# 3_pure60-WKL_mcu.net
KiCad netlist of a schematic drawn in Altium Designer
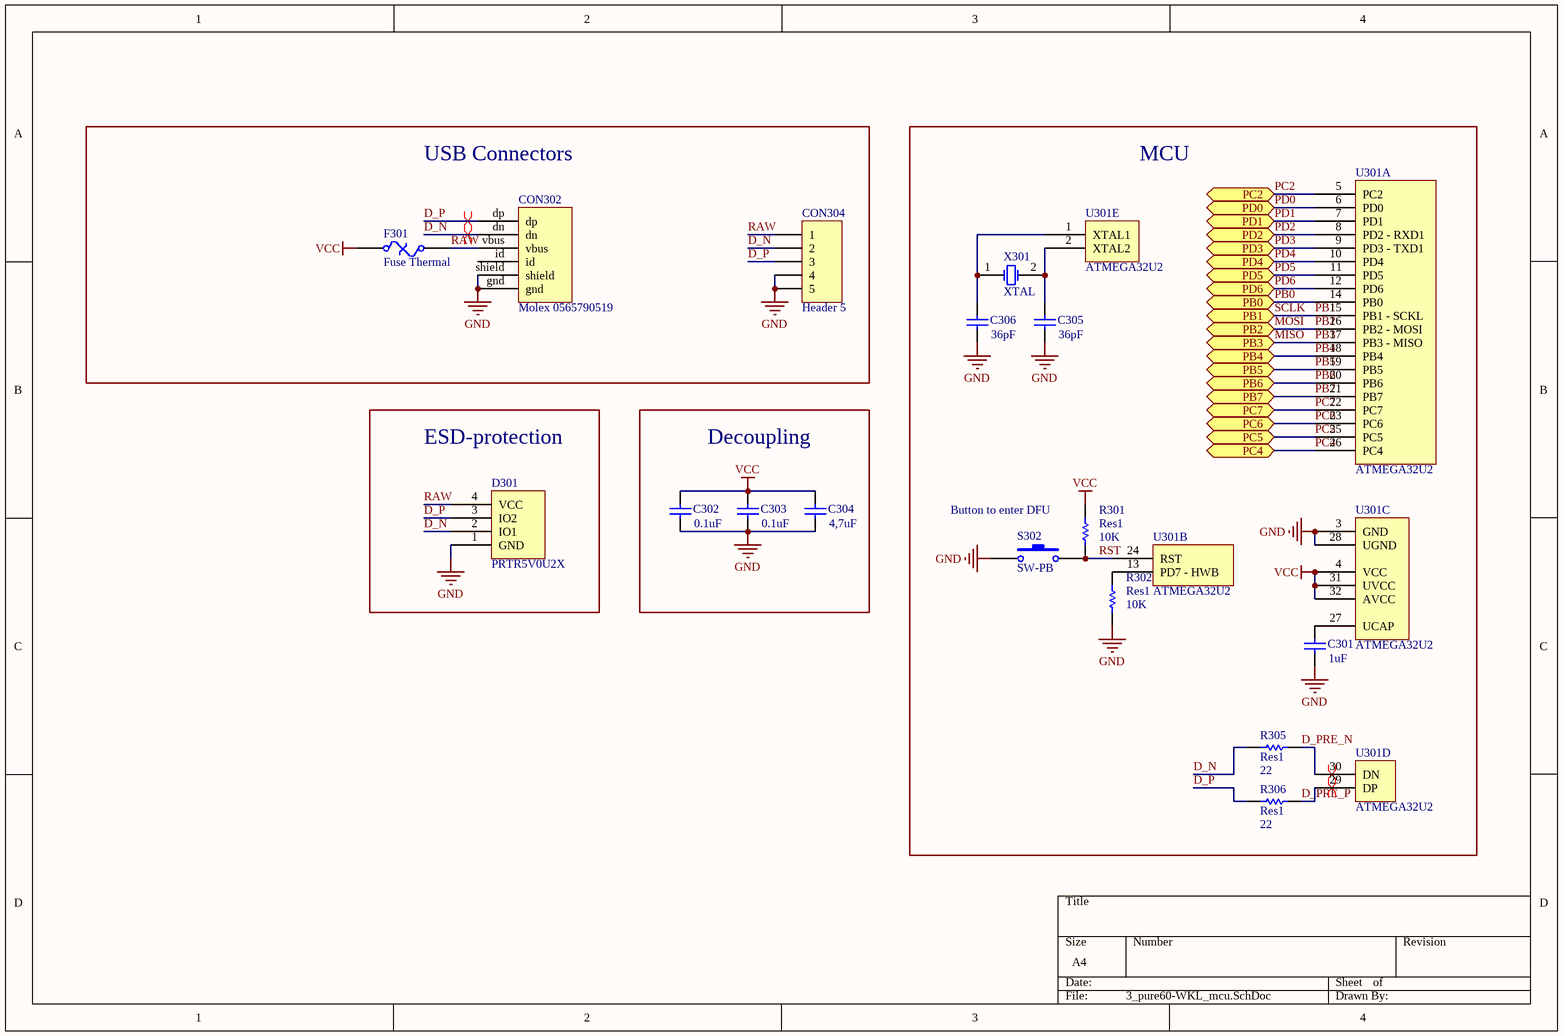
[diagram p0: 3_pure60-WKL_mcu.SchDoc]

(export (version "E")
  (design (tool "Eeschema 10.0.6"))
  (components
    (comp (ref "C301")
      (value "1uF")
      (footprint "C0603[1608]")
      (description "Capacitor")
      (fields (field (name "MFG") "KEMET") (field (name "MRF.PART") "CL10A105KB8NNNC"))
      (libsource (lib "Miscellaneous Devices") (part "Cap"))
    )
    (comp (ref "C302")
      (value "0.1uF")
      (footprint "C0603[1608]")
      (description "Capacitor")
      (fields (field (name "MFG") "KEMET") (field (name "MRF.PART") "CC0603KRX7R9BB104"))
      (libsource (lib "Miscellaneous Devices") (part "Cap"))
    )
    (comp (ref "C303")
      (value "0.1uF")
      (footprint "C0603[1608]")
      (description "Capacitor")
      (fields (field (name "MFG") "KEMET") (field (name "MRF.PART") "CC0603KRX7R9BB104"))
      (libsource (lib "Miscellaneous Devices") (part "Cap"))
    )
    (comp (ref "C304")
      (value "4,7uF")
      (footprint "C1206[3216]")
      (description "Capacitor")
      (fields (field (name "MFG") "KEMET") (field (name "MRF.PART") "1206B475K500NT"))
      (libsource (lib "Miscellaneous Devices") (part "Cap"))
    )
    (comp (ref "C305")
      (value "36pF")
      (footprint "C0603[1608]")
      (description "Capacitor")
      (fields (field (name "MFG") "KEMET") (field (name "MRF.PART") "CL10C360JB8NNNC"))
      (libsource (lib "Miscellaneous Devices") (part "Cap"))
    )
    (comp (ref "C306")
      (value "36pF")
      (footprint "C0603[1608]")
      (description "Capacitor")
      (fields (field (name "MFG") "KEMET") (field (name "MRF.PART") "CL10C360JB8NNNC"))
      (libsource (lib "Miscellaneous Devices") (part "Cap"))
    )
    (comp (ref "CON302")
      (value "Molex 0565790519")
      (footprint "Molex 0565790519")
      (libsource (lib "Keebs") (part "Molex 0565790519"))
    )
    (comp (ref "CON304")
      (value "Header 5")
      (footprint "JST SM04B-SRSS-TB")
      (description "JST for USB daughter board")
      (fields (field (name "MFG") "JST Sales America Inc.") (field (name "MRF.PART") "SM04B-SRSS-TB(LF)(SN)"))
      (libsource (lib "Miscellaneous Connectors") (part "Header 5"))
    )
    (comp (ref "D301")
      (value "PRTR5V0U2X")
      (footprint "SOT190P237X120-4N")
      (fields (field (name "MFG") "Nexperia USA Inc.") (field (name "MRF.PART") "UET14A05L03"))
      (libsource (lib "Schlib1") (part "PRTR5V0U2X"))
    )
    (comp (ref "F301")
      (value "Fuse Thermal")
      (footprint "C1206[3216]")
      (description "Thermal Fuse")
      (fields (field (name "MFG") "Bel Fuse Inc.") (field (name "MRF.PART") "ASMD1206-050"))
      (libsource (lib "Miscellaneous Devices") (part "Fuse Thermal"))
    )
    (comp (ref "R301")
      (value "Res1")
      (footprint "R0603[1608]")
      (description "Resistor")
      (fields
        (field (name "ALTIUM_VALUE") "10K")
        (field (name "MFG") "Panasonic Electronic Components")
        (field (name "MRF.PART") "0603WAF1002T5E")
      )
      (libsource (lib "Miscellaneous Devices") (part "Res1"))
    )
    (comp (ref "R302")
      (value "Res1")
      (footprint "R0603[1608]")
      (description "Resistor")
      (fields
        (field (name "ALTIUM_VALUE") "10K")
        (field (name "MFG") "Panasonic Electronic Components")
        (field (name "MRF.PART") "0603WAF1002T5E")
      )
      (libsource (lib "Miscellaneous Devices") (part "Res1"))
    )
    (comp (ref "R305")
      (value "Res1")
      (footprint "R0603[1608]")
      (description "Resistor")
      (fields
        (field (name "ALTIUM_VALUE") "22")
        (field (name "MFG") "Panasonic Electronic Components")
        (field (name "MRF.PART") "0603WAF220JT5E")
      )
      (libsource (lib "Miscellaneous Devices") (part "Res1"))
    )
    (comp (ref "R306")
      (value "Res1")
      (footprint "R0603[1608]")
      (description "Resistor")
      (fields
        (field (name "ALTIUM_VALUE") "22")
        (field (name "MFG") "Panasonic Electronic Components")
        (field (name "MRF.PART") "0603WAF220JT5E")
      )
      (libsource (lib "Miscellaneous Devices") (part "Res1"))
    )
    (comp (ref "S302")
      (value "SW-PB")
      (footprint "Combo switch")
      (description "Switch")
      (fields (field (name "MFG") "C&K") (field (name "MRF.PART") "TS-1187A-C-D-B"))
      (libsource (lib "Miscellaneous Devices") (part "SW-PB"))
    )
    (comp (ref "U301")
      (value "ATMEGA32U2")
      (footprint "ATMEGA32U2-QFN")
      (fields (field (name "MFG") "Microchip Technology") (field (name "MRF.PART") "ATMEGA32U2-MU"))
      (libsource (lib "") (part "ATMEGA32U2_1"))
    )
    (comp (ref "X301")
      (value "XTAL")
      (footprint "CTS 445-series crystal")
      (description "Crystal Oscillator")
      (fields (field (name "MRF.PART") "X503216MSB2GI"))
      (libsource (lib "Miscellaneous Devices") (part "XTAL"))
    )
  )
  (nets
    (net (code "1") (name "/D_N") (class "Default")
      (node (ref "CON302") (pin "dn") (pinfunction "dn_dn") (pintype "passive"))
      (node (ref "CON304") (pin "2") (pinfunction "2_2") (pintype "passive"))
      (node (ref "D301") (pin "2") (pinfunction "IO1_2") (pintype "passive"))
      (node (ref "R305") (pin "2") (pinfunction "2_2") (pintype "passive"))
    )
    (net (code "2") (name "/D_P") (class "Default")
      (node (ref "CON302") (pin "dp") (pinfunction "dp_dp") (pintype "passive"))
      (node (ref "CON304") (pin "3") (pinfunction "3_3") (pintype "passive"))
      (node (ref "D301") (pin "3") (pinfunction "IO2_3") (pintype "passive"))
      (node (ref "R306") (pin "2") (pinfunction "2_2") (pintype "passive"))
    )
    (net (code "3") (name "/D_PRE_N") (class "Default")
      (node (ref "R305") (pin "1") (pinfunction "1_1") (pintype "passive"))
      (node (ref "U301") (pin "30") (pinfunction "DN_30") (pintype "passive"))
    )
    (net (code "4") (name "/D_PRE_P") (class "Default")
      (node (ref "R306") (pin "1") (pinfunction "1_1") (pintype "passive"))
      (node (ref "U301") (pin "29") (pinfunction "DP_29") (pintype "passive"))
    )
    (net (code "5") (name "/MISO") (class "Default")
      (node (ref "U301") (pin "17") (pinfunction "PB3_-_MISO_17") (pintype "passive"))
    )
    (net (code "6") (name "/MOSI") (class "Default")
      (node (ref "U301") (pin "16") (pinfunction "PB2_-_MOSI_16") (pintype "passive"))
    )
    (net (code "7") (name "/PB0") (class "Default")
      (node (ref "U301") (pin "14") (pinfunction "PB0_14") (pintype "passive"))
    )
    (net (code "8") (name "/PB1") (class "Default")
      (node (ref "U301") (pin "15") (pinfunction "PB1_-_SCKL_15") (pintype "passive"))
    )
    (net (code "9") (name "/PB4") (class "Default")
      (node (ref "U301") (pin "18") (pinfunction "PB4_18") (pintype "passive"))
    )
    (net (code "10") (name "/PB5") (class "Default")
      (node (ref "U301") (pin "19") (pinfunction "PB5_19") (pintype "passive"))
    )
    (net (code "11") (name "/PB6") (class "Default")
      (node (ref "U301") (pin "20") (pinfunction "PB6_20") (pintype "passive"))
    )
    (net (code "12") (name "/PB7") (class "Default")
      (node (ref "U301") (pin "21") (pinfunction "PB7_21") (pintype "passive"))
    )
    (net (code "13") (name "/PC2") (class "Default")
      (node (ref "U301") (pin "5") (pinfunction "PC2_5") (pintype "passive"))
    )
    (net (code "14") (name "/PC4") (class "Default")
      (node (ref "U301") (pin "26") (pinfunction "PC4_26") (pintype "passive"))
    )
    (net (code "15") (name "/PC5") (class "Default")
      (node (ref "U301") (pin "25") (pinfunction "PC5_25") (pintype "passive"))
    )
    (net (code "16") (name "/PC6") (class "Default")
      (node (ref "U301") (pin "23") (pinfunction "PC6_23") (pintype "passive"))
    )
    (net (code "17") (name "/PC7") (class "Default")
      (node (ref "U301") (pin "22") (pinfunction "PC7_22") (pintype "passive"))
    )
    (net (code "18") (name "/PD0") (class "Default")
      (node (ref "U301") (pin "6") (pinfunction "PD0_6") (pintype "passive"))
    )
    (net (code "19") (name "/PD1") (class "Default")
      (node (ref "U301") (pin "7") (pinfunction "PD1_7") (pintype "passive"))
    )
    (net (code "20") (name "/PD2") (class "Default")
      (node (ref "U301") (pin "8") (pinfunction "PD2_-_RXD1_8") (pintype "passive"))
    )
    (net (code "21") (name "/PD3") (class "Default")
      (node (ref "U301") (pin "9") (pinfunction "PD3_-_TXD1_9") (pintype "passive"))
    )
    (net (code "22") (name "/PD4") (class "Default")
      (node (ref "U301") (pin "10") (pinfunction "PD4_10") (pintype "passive"))
    )
    (net (code "23") (name "/PD5") (class "Default")
      (node (ref "U301") (pin "11") (pinfunction "PD5_11") (pintype "passive"))
    )
    (net (code "24") (name "/PD6") (class "Default")
      (node (ref "U301") (pin "12") (pinfunction "PD6_12") (pintype "passive"))
    )
    (net (code "25") (name "/RAW") (class "Default")
      (node (ref "CON302") (pin "vbus") (pinfunction "vbus_vbus") (pintype "passive"))
      (node (ref "CON304") (pin "1") (pinfunction "1_1") (pintype "passive"))
      (node (ref "D301") (pin "4") (pinfunction "VCC_4") (pintype "passive"))
      (node (ref "F301") (pin "2") (pinfunction "2_2") (pintype "passive"))
    )
    (net (code "26") (name "/RST") (class "Default")
      (node (ref "R301") (pin "2") (pinfunction "2_2") (pintype "passive"))
      (node (ref "S302") (pin "2") (pinfunction "2_2") (pintype "passive"))
      (node (ref "U301") (pin "24") (pinfunction "RST_24") (pintype "passive"))
    )
    (net (code "27") (name "GND") (class "Default")
      (node (ref "C301") (pin "1") (pinfunction "1_1") (pintype "passive"))
      (node (ref "C302") (pin "1") (pinfunction "1_1") (pintype "passive"))
      (node (ref "C303") (pin "1") (pinfunction "1_1") (pintype "passive"))
      (node (ref "C304") (pin "1") (pinfunction "1_1") (pintype "passive"))
      (node (ref "C305") (pin "1") (pinfunction "1_1") (pintype "passive"))
      (node (ref "C306") (pin "1") (pinfunction "1_1") (pintype "passive"))
      (node (ref "CON302") (pin "gnd") (pinfunction "gnd_gnd") (pintype "passive"))
      (node (ref "CON302") (pin "shield") (pinfunction "shield_shield") (pintype "passive"))
      (node (ref "CON304") (pin "4") (pinfunction "4_4") (pintype "passive"))
      (node (ref "CON304") (pin "5") (pinfunction "5_5") (pintype "passive"))
      (node (ref "D301") (pin "1") (pinfunction "GND_1") (pintype "passive"))
      (node (ref "R302") (pin "2") (pinfunction "2_2") (pintype "passive"))
      (node (ref "S302") (pin "1") (pinfunction "1_1") (pintype "passive"))
      (node (ref "U301") (pin "28") (pinfunction "UGND_28") (pintype "passive"))
      (node (ref "U301") (pin "3") (pinfunction "GND_3") (pintype "passive"))
    )
    (net (code "28") (name "Net-(U301B-PD7_-_HWB)") (class "Default")
      (node (ref "R302") (pin "1") (pinfunction "1_1") (pintype "passive"))
      (node (ref "U301") (pin "13") (pinfunction "PD7_-_HWB_13") (pintype "passive"))
    )
    (net (code "29") (name "Net-(U301C-UCAP)") (class "Default")
      (node (ref "C301") (pin "2") (pinfunction "2_2") (pintype "passive"))
      (node (ref "U301") (pin "27") (pinfunction "UCAP_27") (pintype "passive"))
    )
    (net (code "30") (name "Net-(U301E-XTAL1)") (class "Default")
      (node (ref "C306") (pin "2") (pinfunction "2_2") (pintype "passive"))
      (node (ref "U301") (pin "1") (pinfunction "XTAL1_1") (pintype "passive"))
      (node (ref "X301") (pin "1") (pinfunction "OSC1_1") (pintype "passive"))
    )
    (net (code "31") (name "Net-(U301E-XTAL2)") (class "Default")
      (node (ref "C305") (pin "2") (pinfunction "2_2") (pintype "passive"))
      (node (ref "U301") (pin "2") (pinfunction "XTAL2_2") (pintype "passive"))
      (node (ref "X301") (pin "2") (pinfunction "OSC2_2") (pintype "passive"))
    )
    (net (code "32") (name "VCC") (class "Default")
      (node (ref "C302") (pin "2") (pinfunction "2_2") (pintype "passive"))
      (node (ref "C303") (pin "2") (pinfunction "2_2") (pintype "passive"))
      (node (ref "C304") (pin "2") (pinfunction "2_2") (pintype "passive"))
      (node (ref "F301") (pin "1") (pinfunction "1_1") (pintype "passive"))
      (node (ref "R301") (pin "1") (pinfunction "1_1") (pintype "passive"))
      (node (ref "U301") (pin "31") (pinfunction "UVCC_31") (pintype "passive"))
      (node (ref "U301") (pin "32") (pinfunction "AVCC_32") (pintype "passive"))
      (node (ref "U301") (pin "4") (pinfunction "VCC_4") (pintype "passive"))
    )
    (net (code "33") (name "unconnected-(CON302-Padid)") (class "Default")
      (node (ref "CON302") (pin "id") (pinfunction "id_id") (pintype "passive"))
    )
  )
)
